# AuxhalfH.net
KiCad netlist of a schematic drawn in Altium Designer
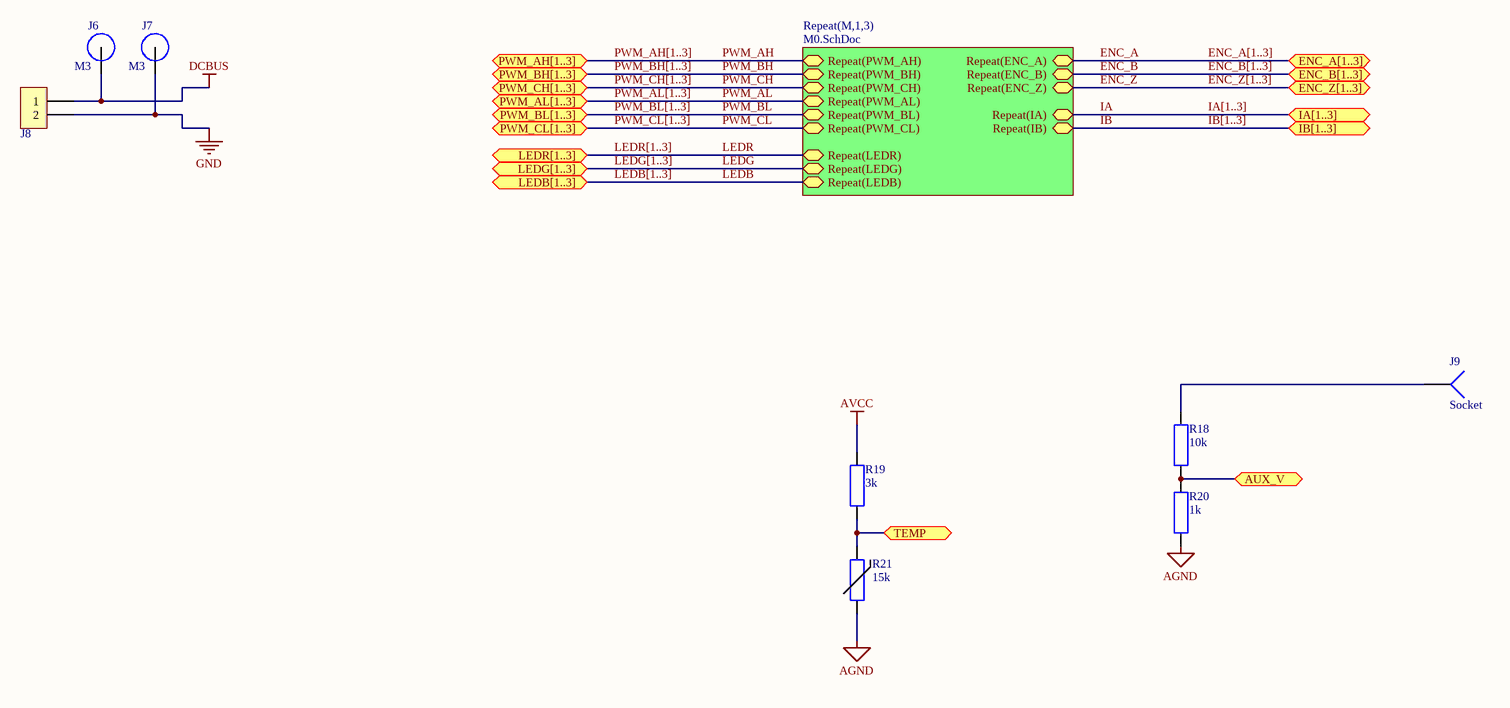
[diagram p0: AuxhalfH.SchDoc]

(export (version "E")
  (design (tool "Eeschema 10.0.6"))
  (components
    (comp (ref "J6")
      (value "M3")
      (footprint "M3 Spade Hole")
      (description "M3 Spade Terminal")
      (libsource (lib "CustomComponents") (part "M3 Spade Terminal"))
    )
    (comp (ref "J7")
      (value "M3")
      (footprint "M3 Spade Hole")
      (description "M3 Spade Terminal")
      (libsource (lib "CustomComponents") (part "M3 Spade Terminal"))
    )
    (comp (ref "J8")
      (value "MC000232")
      (footprint "MC000232")
      (description "TERMINAL BLOCK, WIRE TO BRD, 2POS, 6AWG")
      (libsource (lib "CustomComponents") (part "MC000232"))
    )
    (comp (ref "J9")
      (value "Socket")
      (footprint "PIN1")
      (fields (field (name "PUBLISHER") "Altium Limited"))
      (libsource (lib "Miscellaneous Connectors") (part "Socket"))
    )
    (comp (ref "R18")
      (value "10k")
      (footprint "RESC1608X06L")
      (description "Resistor, 10k, 0603")
      (fields (field (name "Comment") "MCMR06X1002FTL"))
      (libsource (lib "CustomComponents") (part "MCMR06X1002FTL"))
    )
    (comp (ref "R19")
      (value "3k")
      (footprint "RESC1608X55N")
      (description "RESISTOR, 0603, 3K, 1%, ANTI SULFUR")
      (fields (field (name "Comment") "MCMR06X3001FTL"))
      (libsource (lib "CustomComponents") (part "MCMR06X3001FTL"))
    )
    (comp (ref "R20")
      (value "1k")
      (footprint "RESC1608X55N")
      (description "RESISTOR, CERAMIC, 1K, 0.1W, 1%")
      (fields (field (name "Comment") "MCMR06X1001FTL"))
      (libsource (lib "CustomComponents") (part "MCMR06X1001FTL"))
    )
    (comp (ref "R21")
      (value "15k")
      (footprint "RESC1608X06L")
      (description "THERMISTOR, 15K, 5%, SMD, NTC")
      (fields (field (name "Comment") "NTCS0603E3153JMT"))
      (libsource (lib "CustomComponents") (part "NTCS0603E3153JMT"))
    )
  )
  (nets
    (net (code "43") (name "/AUX_V") (class "Default")
      (node (ref "R18") (pin "1") (pinfunction "0_1") (pintype "passive"))
      (node (ref "R20") (pin "2") (pinfunction "0_2") (pintype "passive"))
    )
    (net (code "72") (name "/TEMP") (class "Default")
      (node (ref "R19") (pin "1") (pinfunction "0_1") (pintype "passive"))
      (node (ref "R21") (pin "2") (pinfunction "0_2") (pintype "passive"))
    )
    (net (code "73") (name "AGND") (class "Default")
      (node (ref "R20") (pin "1") (pinfunction "0_1") (pintype "passive"))
      (node (ref "R21") (pin "1") (pinfunction "0_1") (pintype "passive"))
    )
    (net (code "74") (name "AVCC") (class "Default")
      (node (ref "R19") (pin "2") (pinfunction "0_2") (pintype "passive"))
    )
    (net (code "75") (name "DCBUS") (class "Default")
      (node (ref "J6") (pin "1") (pinfunction "1_1") (pintype "passive"))
      (node (ref "J8") (pin "1") (pinfunction "1_1") (pintype "passive"))
    )
    (net (code "76") (name "GND") (class "Default")
      (node (ref "J7") (pin "1") (pinfunction "1_1") (pintype "passive"))
      (node (ref "J8") (pin "2") (pinfunction "2_2") (pintype "passive"))
    )
    (net (code "77") (name "Net-(J9-Pad1)") (class "Default")
      (node (ref "J9") (pin "1") (pinfunction "1_1") (pintype "passive"))
      (node (ref "R18") (pin "2") (pinfunction "0_2") (pintype "passive"))
    )
  )
)
